# 2-STM32H563.net
KiCad netlist of a schematic drawn in Altium Designer
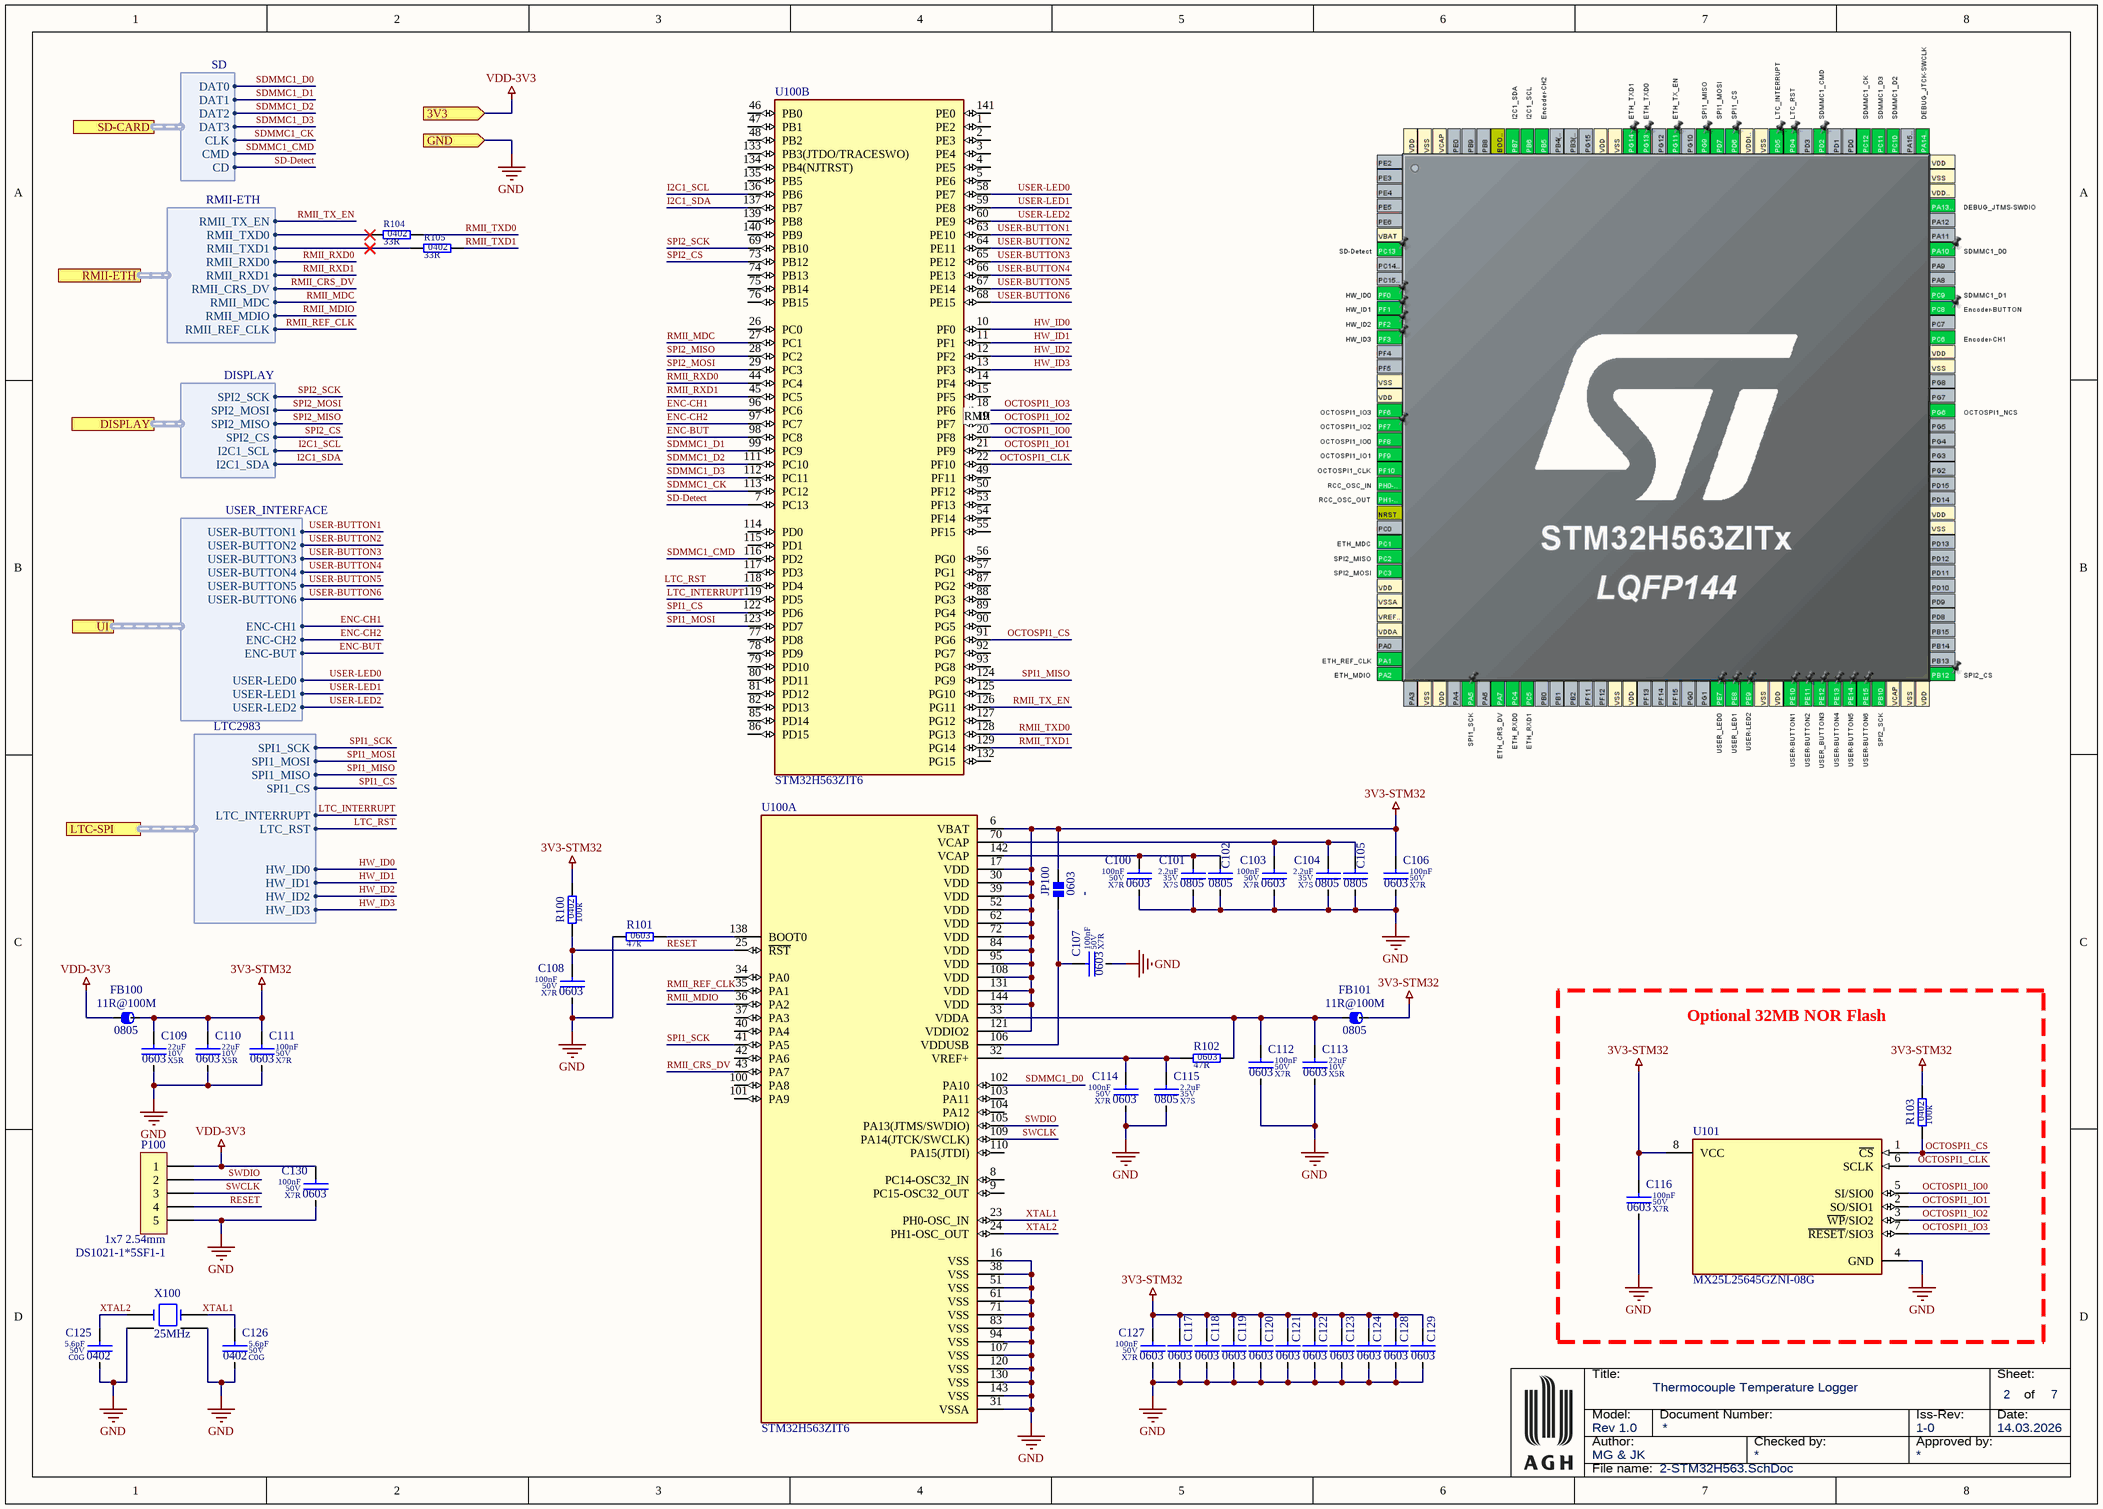
[diagram p0: 2-STM32H563.SchDoc]

(export (version "E")
  (design (tool "Eeschema 10.0.6"))
  (components
    (comp (ref "C100")
      (value "100nF")
      (footprint "C_0603_1608")
      (description "Capacitor")
      (fields
        (field (name "DIELECTRIC") "X7R")
        (field (name "VOLTAGE") "50V")
        (field (name "SCH_FOOTPRINT") "0603")
        (field (name "PART NUMBER") "C_100nF_50V_X7R_0603_10_AECQ1")
        (field (name "MANUFACTURER") "Murata")
      )
      (libsource (lib "Library") (part "C"))
    )
    (comp (ref "C101")
      (value "2.2uF")
      (footprint "C_0805_2012")
      (description "Capacitor")
      (fields
        (field (name "DIELECTRIC") "X7S")
        (field (name "VOLTAGE") "35V")
        (field (name "SCH_FOOTPRINT") "0805")
        (field (name "PART NUMBER") "C_2.2uF_35V_X7S_0805_10_AECQ1")
        (field (name "MANUFACTURER") "Murata")
      )
      (libsource (lib "Library") (part "C"))
    )
    (comp (ref "C102")
      (value "Ceramic X7S")
      (footprint "C_0805_2012")
      (description "Capacitor")
      (fields
        (field (name "VOLTAGE") "35V")
        (field (name "SCH_FOOTPRINT") "0805")
        (field (name "PART NUMBER") "C_2.2uF_35V_X7S_0805_10_AECQ1")
      )
      (libsource (lib "Library") (part "C"))
    )
    (comp (ref "C103")
      (value "100nF")
      (footprint "C_0603_1608")
      (description "Capacitor")
      (fields
        (field (name "DIELECTRIC") "X7R")
        (field (name "VOLTAGE") "50V")
        (field (name "SCH_FOOTPRINT") "0603")
        (field (name "PART NUMBER") "C_100nF_50V_X7R_0603_10_AECQ1")
        (field (name "MANUFACTURER") "Murata")
      )
      (libsource (lib "Library") (part "C"))
    )
    (comp (ref "C104")
      (value "2.2uF")
      (footprint "C_0805_2012")
      (description "Capacitor")
      (fields
        (field (name "DIELECTRIC") "X7S")
        (field (name "VOLTAGE") "35V")
        (field (name "SCH_FOOTPRINT") "0805")
        (field (name "PART NUMBER") "C_2.2uF_35V_X7S_0805_10_AECQ1")
        (field (name "MANUFACTURER") "Murata")
      )
      (libsource (lib "Library") (part "C"))
    )
    (comp (ref "C105")
      (value "Ceramic X7S")
      (footprint "C_0805_2012")
      (description "Capacitor")
      (fields
        (field (name "VOLTAGE") "35V")
        (field (name "SCH_FOOTPRINT") "0805")
        (field (name "PART NUMBER") "C_2.2uF_35V_X7S_0805_10_AECQ1")
      )
      (libsource (lib "Library") (part "C"))
    )
    (comp (ref "C106")
      (value "100nF")
      (footprint "C_0603_1608")
      (description "Capacitor")
      (fields
        (field (name "DIELECTRIC") "X7R")
        (field (name "VOLTAGE") "50V")
        (field (name "SCH_FOOTPRINT") "0603")
        (field (name "PART NUMBER") "C_100nF_50V_X7R_0603_10_AECQ1")
        (field (name "MANUFACTURER") "Murata")
      )
      (libsource (lib "Library") (part "C"))
    )
    (comp (ref "C107")
      (value "100nF")
      (footprint "C_0603_1608")
      (description "Capacitor")
      (fields
        (field (name "DIELECTRIC") "X7R")
        (field (name "VOLTAGE") "50V")
        (field (name "SCH_FOOTPRINT") "0603")
        (field (name "PART NUMBER") "C_100nF_50V_X7R_0603_10_AECQ1")
        (field (name "MANUFACTURER") "Murata")
      )
      (libsource (lib "Library") (part "C"))
    )
    (comp (ref "C108")
      (value "100nF")
      (footprint "C_0603_1608")
      (description "Capacitor")
      (fields
        (field (name "DIELECTRIC") "X7R")
        (field (name "VOLTAGE") "50V")
        (field (name "SCH_FOOTPRINT") "0603")
        (field (name "PART NUMBER") "C_100nF_50V_X7R_0603_10_AECQ1")
        (field (name "MANUFACTURER") "Murata")
      )
      (libsource (lib "Library") (part "C"))
    )
    (comp (ref "C109")
      (value "22uF")
      (footprint "C_0603_1608")
      (description "Capacitor")
      (fields
        (field (name "DIELECTRIC") "X5R")
        (field (name "VOLTAGE") "10V")
        (field (name "SCH_FOOTPRINT") "0603")
        (field (name "PART NUMBER") "C_22uF_10V_X5R_0603_20")
        (field (name "MANUFACTURER") "Murata")
      )
      (libsource (lib "Library") (part "C"))
    )
    (comp (ref "C110")
      (value "22uF")
      (footprint "C_0603_1608")
      (description "Capacitor")
      (fields
        (field (name "DIELECTRIC") "X5R")
        (field (name "VOLTAGE") "10V")
        (field (name "SCH_FOOTPRINT") "0603")
        (field (name "PART NUMBER") "C_22uF_10V_X5R_0603_20")
        (field (name "MANUFACTURER") "Murata")
      )
      (libsource (lib "Library") (part "C"))
    )
    (comp (ref "C111")
      (value "100nF")
      (footprint "C_0603_1608")
      (description "Capacitor")
      (fields
        (field (name "DIELECTRIC") "X7R")
        (field (name "VOLTAGE") "50V")
        (field (name "SCH_FOOTPRINT") "0603")
        (field (name "PART NUMBER") "C_100nF_50V_X7R_0603_10_AECQ1")
        (field (name "MANUFACTURER") "Murata")
      )
      (libsource (lib "Library") (part "C"))
    )
    (comp (ref "C112")
      (value "100nF")
      (footprint "C_0603_1608")
      (description "Capacitor")
      (fields
        (field (name "DIELECTRIC") "X7R")
        (field (name "VOLTAGE") "50V")
        (field (name "SCH_FOOTPRINT") "0603")
        (field (name "PART NUMBER") "C_100nF_50V_X7R_0603_10_AECQ1")
        (field (name "MANUFACTURER") "Murata")
      )
      (libsource (lib "Library") (part "C"))
    )
    (comp (ref "C113")
      (value "22uF")
      (footprint "C_0603_1608")
      (description "Capacitor")
      (fields
        (field (name "DIELECTRIC") "X5R")
        (field (name "VOLTAGE") "10V")
        (field (name "SCH_FOOTPRINT") "0603")
        (field (name "PART NUMBER") "C_22uF_10V_X5R_0603_20")
        (field (name "MANUFACTURER") "Murata")
      )
      (libsource (lib "Library") (part "C"))
    )
    (comp (ref "C114")
      (value "100nF")
      (footprint "C_0603_1608")
      (description "Capacitor")
      (fields
        (field (name "DIELECTRIC") "X7R")
        (field (name "VOLTAGE") "50V")
        (field (name "SCH_FOOTPRINT") "0603")
        (field (name "PART NUMBER") "C_100nF_50V_X7R_0603_10_AECQ1")
        (field (name "MANUFACTURER") "Murata")
      )
      (libsource (lib "Library") (part "C"))
    )
    (comp (ref "C115")
      (value "2.2uF")
      (footprint "C_0805_2012")
      (description "Capacitor")
      (fields
        (field (name "DIELECTRIC") "X7S")
        (field (name "VOLTAGE") "35V")
        (field (name "SCH_FOOTPRINT") "0805")
        (field (name "PART NUMBER") "C_2.2uF_35V_X7S_0805_10_AECQ1")
        (field (name "MANUFACTURER") "Murata")
      )
      (libsource (lib "Library") (part "C"))
    )
    (comp (ref "C116")
      (value "100nF")
      (footprint "C_0603_1608")
      (description "Capacitor")
      (fields
        (field (name "DIELECTRIC") "X7R")
        (field (name "VOLTAGE") "50V")
        (field (name "SCH_FOOTPRINT") "0603")
        (field (name "PART NUMBER") "C_100nF_50V_X7R_0603_10_AECQ1")
        (field (name "MANUFACTURER") "Murata")
      )
      (libsource (lib "Library") (part "C"))
    )
    (comp (ref "C117")
      (value "Ceramic X7R")
      (footprint "C_0603_1608")
      (description "Capacitor")
      (fields
        (field (name "VOLTAGE") "50V")
        (field (name "SCH_FOOTPRINT") "0603")
        (field (name "PART NUMBER") "C_100nF_50V_X7R_0603_10_AECQ1")
      )
      (libsource (lib "Library") (part "C"))
    )
    (comp (ref "C118")
      (value "Ceramic X7R")
      (footprint "C_0603_1608")
      (description "Capacitor")
      (fields
        (field (name "VOLTAGE") "50V")
        (field (name "SCH_FOOTPRINT") "0603")
        (field (name "PART NUMBER") "C_100nF_50V_X7R_0603_10_AECQ1")
      )
      (libsource (lib "Library") (part "C"))
    )
    (comp (ref "C119")
      (value "Ceramic X7R")
      (footprint "C_0603_1608")
      (description "Capacitor")
      (fields
        (field (name "VOLTAGE") "50V")
        (field (name "SCH_FOOTPRINT") "0603")
        (field (name "PART NUMBER") "C_100nF_50V_X7R_0603_10_AECQ1")
      )
      (libsource (lib "Library") (part "C"))
    )
    (comp (ref "C120")
      (value "Ceramic X7R")
      (footprint "C_0603_1608")
      (description "Capacitor")
      (fields
        (field (name "VOLTAGE") "50V")
        (field (name "SCH_FOOTPRINT") "0603")
        (field (name "PART NUMBER") "C_100nF_50V_X7R_0603_10_AECQ1")
      )
      (libsource (lib "Library") (part "C"))
    )
    (comp (ref "C121")
      (value "Ceramic X7R")
      (footprint "C_0603_1608")
      (description "Capacitor")
      (fields
        (field (name "VOLTAGE") "50V")
        (field (name "SCH_FOOTPRINT") "0603")
        (field (name "PART NUMBER") "C_100nF_50V_X7R_0603_10_AECQ1")
      )
      (libsource (lib "Library") (part "C"))
    )
    (comp (ref "C122")
      (value "Ceramic X7R")
      (footprint "C_0603_1608")
      (description "Capacitor")
      (fields
        (field (name "VOLTAGE") "50V")
        (field (name "SCH_FOOTPRINT") "0603")
        (field (name "PART NUMBER") "C_100nF_50V_X7R_0603_10_AECQ1")
      )
      (libsource (lib "Library") (part "C"))
    )
    (comp (ref "C123")
      (value "Ceramic X7R")
      (footprint "C_0603_1608")
      (description "Capacitor")
      (fields
        (field (name "VOLTAGE") "50V")
        (field (name "SCH_FOOTPRINT") "0603")
        (field (name "PART NUMBER") "C_100nF_50V_X7R_0603_10_AECQ1")
      )
      (libsource (lib "Library") (part "C"))
    )
    (comp (ref "C124")
      (value "Ceramic X7R")
      (footprint "C_0603_1608")
      (description "Capacitor")
      (fields
        (field (name "VOLTAGE") "50V")
        (field (name "SCH_FOOTPRINT") "0603")
        (field (name "PART NUMBER") "C_100nF_50V_X7R_0603_10_AECQ1")
      )
      (libsource (lib "Library") (part "C"))
    )
    (comp (ref "C125")
      (value "5.6pF")
      (footprint "C_0402_1005")
      (description "Capacitor")
      (fields
        (field (name "DIELECTRIC") "C0G")
        (field (name "VOLTAGE") "50V")
        (field (name "SCH_FOOTPRINT") "0402")
        (field (name "PART NUMBER") "C_5.6pF_50V_C0G_0402_2_AECQ1")
        (field (name "MANUFACTURER") "Murata")
      )
      (libsource (lib "Library") (part "C"))
    )
    (comp (ref "C126")
      (value "5.6pF")
      (footprint "C_0402_1005")
      (description "Capacitor")
      (fields
        (field (name "DIELECTRIC") "C0G")
        (field (name "VOLTAGE") "50V")
        (field (name "SCH_FOOTPRINT") "0402")
        (field (name "PART NUMBER") "C_5.6pF_50V_C0G_0402_2_AECQ1")
        (field (name "MANUFACTURER") "Murata")
      )
      (libsource (lib "Library") (part "C"))
    )
    (comp (ref "C127")
      (value "100nF")
      (footprint "C_0603_1608")
      (description "Capacitor")
      (fields
        (field (name "DIELECTRIC") "X7R")
        (field (name "VOLTAGE") "50V")
        (field (name "SCH_FOOTPRINT") "0603")
        (field (name "PART NUMBER") "C_100nF_50V_X7R_0603_10_AECQ1")
        (field (name "MANUFACTURER") "Murata")
      )
      (libsource (lib "Library") (part "C"))
    )
    (comp (ref "C128")
      (value "Ceramic X7R")
      (footprint "C_0603_1608")
      (description "Capacitor")
      (fields
        (field (name "VOLTAGE") "50V")
        (field (name "SCH_FOOTPRINT") "0603")
        (field (name "PART NUMBER") "C_100nF_50V_X7R_0603_10_AECQ1")
      )
      (libsource (lib "Library") (part "C"))
    )
    (comp (ref "C129")
      (value "Ceramic X7R")
      (footprint "C_0603_1608")
      (description "Capacitor")
      (fields
        (field (name "VOLTAGE") "50V")
        (field (name "SCH_FOOTPRINT") "0603")
        (field (name "PART NUMBER") "C_100nF_50V_X7R_0603_10_AECQ1")
      )
      (libsource (lib "Library") (part "C"))
    )
    (comp (ref "C130")
      (value "100nF")
      (footprint "C_0603_1608")
      (description "Capacitor")
      (fields
        (field (name "DIELECTRIC") "X7R")
        (field (name "VOLTAGE") "50V")
        (field (name "SCH_FOOTPRINT") "0603")
        (field (name "PART NUMBER") "C_100nF_50V_X7R_0603_10_AECQ1")
        (field (name "MANUFACTURER") "Murata")
      )
      (libsource (lib "Library") (part "C"))
    )
    (comp (ref "FB100")
      (value "11R@100M")
      (footprint "FB_0805_2012")
      (description "Ferrite Bead")
      (fields
        (field (name "SCH_FOOTPRINT") "0805")
        (field (name "PART NUMBER") "FB_2508051107Y0")
        (field (name "MANUFACTURER") "Fair-Rite")
      )
      (libsource (lib "Library") (part "FB"))
    )
    (comp (ref "FB101")
      (value "11R@100M")
      (footprint "FB_0805_2012")
      (description "Ferrite Bead")
      (fields
        (field (name "SCH_FOOTPRINT") "0805")
        (field (name "PART NUMBER") "FB_2508051107Y0")
        (field (name "MANUFACTURER") "Fair-Rite")
      )
      (libsource (lib "Library") (part "FB"))
    )
    (comp (ref "JP100")
      (value "-")
      (footprint "JP_0603_1608")
      (fields
        (field (name "SCH_FOOTPRINT") "0603")
        (field (name "PART NUMBER") "JP_0603_1608")
        (field (name "Comment") "Solder Jumper 0603/1608")
      )
      (libsource (lib "Library") (part "JP"))
    )
    (comp (ref "P100")
      (value "DS1021-1*5SF1-1")
      (footprint "P_HEADER_1x5_2.54")
      (description "Pin Header")
      (fields
        (field (name "SCH_FOOTPRINT") "1x7 2.54mm")
        (field (name "PART NUMBER") "P_HEADER_1x5_2.54")
        (field (name "MANUFACTURER") "Connfly")
      )
      (libsource (lib "Library") (part "P_HEADER_1x5"))
    )
    (comp (ref "R100")
      (value "100k")
      (footprint "R_0402_1005")
      (fields
        (field (name "SCH_FOOTPRINT") "0402")
        (field (name "PART NUMBER") "R_100k_0402_1")
        (field (name "VOLTAGE") "50V")
        (field (name "POWER") "63mW")
      )
      (libsource (lib "Library") (part "R"))
    )
    (comp (ref "R101")
      (value "47k")
      (footprint "R_0603_1608")
      (fields
        (field (name "SCH_FOOTPRINT") "0603")
        (field (name "PART NUMBER") "R_47k_0603_1_AECQ0")
        (field (name "VOLTAGE") "75V")
        (field (name "POWER") "100mW")
      )
      (libsource (lib "Library") (part "R"))
    )
    (comp (ref "R102")
      (value "47R")
      (footprint "R_0603_1608")
      (fields
        (field (name "SCH_FOOTPRINT") "0603")
        (field (name "PART NUMBER") "R_47R_0603_1")
        (field (name "VOLTAGE") "75V")
        (field (name "POWER") "100mW")
      )
      (libsource (lib "Library") (part "R"))
    )
    (comp (ref "R103")
      (value "100k")
      (footprint "R_0402_1005")
      (fields
        (field (name "SCH_FOOTPRINT") "0402")
        (field (name "PART NUMBER") "R_100k_0402_1")
        (field (name "VOLTAGE") "50V")
        (field (name "POWER") "63mW")
      )
      (libsource (lib "Library") (part "R"))
    )
    (comp (ref "R104")
      (value "33R")
      (footprint "R_0402_1005")
      (fields
        (field (name "SCH_FOOTPRINT") "0402")
        (field (name "PART NUMBER") "R_33R_0402_1_AECQ0")
        (field (name "VOLTAGE") "50V")
        (field (name "POWER") "100mW")
      )
      (libsource (lib "Library") (part "R"))
    )
    (comp (ref "R105")
      (value "33R")
      (footprint "R_0402_1005")
      (fields
        (field (name "SCH_FOOTPRINT") "0402")
        (field (name "PART NUMBER") "R_33R_0402_1_AECQ0")
        (field (name "VOLTAGE") "50V")
        (field (name "POWER") "100mW")
      )
      (libsource (lib "Library") (part "R"))
    )
    (comp (ref "U100")
      (value "STM32H563ZIT6")
      (footprint "QFP50P2200X2200X160-144N")
      (description "ARMÂ® CortexÂ®-M33 STM32H5 Microcontroller IC 32-Bit 250MHz 2MB (2M x 8) FLASH 144-LQFP (20x20)")
      (fields (field (name "MF") "STMicroelectronics"))
      (libsource (lib "STM32H563ZIT6") (part "STM32H563ZIT6"))
    )
    (comp (ref "U101")
      (value "MX25L25645GZNI-08G")
      (footprint "SOIC-8-4X5X18")
      (description "IC FLSH 256MBIT SPI 120MHZ 8WSON")
      (libsource (lib "MX25L25645GM2I-10G") (part "MX25L25645GM2I-10G"))
    )
    (comp (ref "X100")
      (value "25MHz")
      (footprint "X_2x1.6_4PIN")
      (fields
        (field (name "PART NUMBER") "NX2016SA-25.000M-STD-CZS-1")
        (field (name "MANUFACTURER") "NDK")
        (field (name "Comment") "32 MHz Oscilator")
      )
      (libsource (lib "Library") (part "X_GENERIC_4PIN"))
    )
  )
  (nets
    (net (code "6") (name "/ENC-BUT") (class "Default")
      (node (ref "U100") (pin "98") (pinfunction "PC8_98") (pintype "bidirectional"))
    )
    (net (code "7") (name "/ENC-CH1") (class "Default")
      (node (ref "U100") (pin "96") (pinfunction "PC6_96") (pintype "bidirectional"))
    )
    (net (code "8") (name "/ENC-CH2") (class "Default")
      (node (ref "U100") (pin "97") (pinfunction "PC7_97") (pintype "bidirectional"))
    )
    (net (code "9") (name "/HW_ID0") (class "Default")
      (node (ref "U100") (pin "10") (pinfunction "PF0_10") (pintype "bidirectional"))
    )
    (net (code "10") (name "/HW_ID1") (class "Default")
      (node (ref "U100") (pin "11") (pinfunction "PF1_11") (pintype "bidirectional"))
    )
    (net (code "11") (name "/HW_ID2") (class "Default")
      (node (ref "U100") (pin "12") (pinfunction "PF2_12") (pintype "bidirectional"))
    )
    (net (code "12") (name "/HW_ID3") (class "Default")
      (node (ref "U100") (pin "13") (pinfunction "PF3_13") (pintype "bidirectional"))
    )
    (net (code "13") (name "/I2C1_SCL") (class "Default")
      (node (ref "U100") (pin "136") (pinfunction "PB6_136") (pintype "bidirectional"))
    )
    (net (code "14") (name "/I2C1_SDA") (class "Default")
      (node (ref "U100") (pin "137") (pinfunction "PB7_137") (pintype "bidirectional"))
    )
    (net (code "15") (name "/LTC_INTERRUPT") (class "Default")
      (node (ref "U100") (pin "119") (pinfunction "PD5_119") (pintype "bidirectional"))
    )
    (net (code "16") (name "/LTC_RST") (class "Default")
      (node (ref "U100") (pin "118") (pinfunction "PD4_118") (pintype "bidirectional"))
    )
    (net (code "17") (name "/OCTOSPI1_CLK") (class "Default")
      (node (ref "U100") (pin "22") (pinfunction "PF10_22") (pintype "bidirectional"))
      (node (ref "U101") (pin "6") (pinfunction "SCLK_6") (pintype "input"))
    )
    (net (code "18") (name "/OCTOSPI1_CS") (class "Default")
      (node (ref "R103") (pin "1") (pinfunction "1_1") (pintype "passive"))
      (node (ref "U100") (pin "91") (pinfunction "PG6_91") (pintype "bidirectional"))
      (node (ref "U101") (pin "1") (pinfunction "~{CS}_1") (pintype "input"))
    )
    (net (code "19") (name "/OCTOSPI1_IO0") (class "Default")
      (node (ref "U100") (pin "20") (pinfunction "PF8_20") (pintype "bidirectional"))
      (node (ref "U101") (pin "5") (pinfunction "SI/SIO0_5") (pintype "bidirectional"))
    )
    (net (code "20") (name "/OCTOSPI1_IO1") (class "Default")
      (node (ref "U100") (pin "21") (pinfunction "PF9_21") (pintype "bidirectional"))
      (node (ref "U101") (pin "2") (pinfunction "SO/SIO1_2") (pintype "bidirectional"))
    )
    (net (code "21") (name "/OCTOSPI1_IO2") (class "Default")
      (node (ref "U100") (pin "19") (pinfunction "PF7_19") (pintype "bidirectional"))
      (node (ref "U101") (pin "3") (pinfunction "~{WP}/SIO2_3") (pintype "bidirectional"))
    )
    (net (code "22") (name "/OCTOSPI1_IO3") (class "Default")
      (node (ref "U100") (pin "18") (pinfunction "PF6_18") (pintype "bidirectional"))
      (node (ref "U101") (pin "7") (pinfunction "~{RESET}/SIO3_7") (pintype "bidirectional"))
    )
    (net (code "23") (name "/RESET") (class "Default")
      (node (ref "C108") (pin "1") (pinfunction "1_1") (pintype "passive"))
      (node (ref "P100") (pin "4") (pinfunction "4_4") (pintype "passive"))
      (node (ref "R100") (pin "1") (pinfunction "1_1") (pintype "passive"))
      (node (ref "U100") (pin "25") (pinfunction "~{RST}_25") (pintype "bidirectional"))
    )
    (net (code "24") (name "/RMII_CRS_DV") (class "Default")
      (node (ref "U100") (pin "43") (pinfunction "PA7_43") (pintype "bidirectional"))
    )
    (net (code "25") (name "/RMII_MDC") (class "Default")
      (node (ref "U100") (pin "27") (pinfunction "PC1_27") (pintype "bidirectional"))
    )
    (net (code "26") (name "/RMII_MDIO") (class "Default")
      (node (ref "U100") (pin "36") (pinfunction "PA2_36") (pintype "bidirectional"))
    )
    (net (code "27") (name "/RMII_REF_CLK") (class "Default")
      (node (ref "U100") (pin "35") (pinfunction "PA1_35") (pintype "bidirectional"))
    )
    (net (code "28") (name "/RMII_RXD0") (class "Default")
      (node (ref "U100") (pin "44") (pinfunction "PC4_44") (pintype "bidirectional"))
    )
    (net (code "29") (name "/RMII_RXD1") (class "Default")
      (node (ref "U100") (pin "45") (pinfunction "PC5_45") (pintype "bidirectional"))
    )
    (net (code "30") (name "/RMII_TXD0") (class "Default")
      (node (ref "R104") (pin "2") (pinfunction "2_2") (pintype "passive"))
      (node (ref "U100") (pin "128") (pinfunction "PG13_128") (pintype "bidirectional"))
    )
    (net (code "31") (name "/RMII_TXD1") (class "Default")
      (node (ref "R105") (pin "2") (pinfunction "2_2") (pintype "passive"))
      (node (ref "U100") (pin "129") (pinfunction "PG14_129") (pintype "bidirectional"))
    )
    (net (code "32") (name "/RMII_TX_EN") (class "Default")
      (node (ref "U100") (pin "126") (pinfunction "PG11_126") (pintype "bidirectional"))
    )
    (net (code "33") (name "/SD-Detect") (class "Default")
      (node (ref "U100") (pin "7") (pinfunction "PC13_7") (pintype "bidirectional"))
    )
    (net (code "34") (name "/SDMMC1_CK") (class "Default")
      (node (ref "U100") (pin "113") (pinfunction "PC12_113") (pintype "bidirectional"))
    )
    (net (code "35") (name "/SDMMC1_CMD") (class "Default")
      (node (ref "U100") (pin "116") (pinfunction "PD2_116") (pintype "bidirectional"))
    )
    (net (code "36") (name "/SDMMC1_D0") (class "Default")
      (node (ref "U100") (pin "102") (pinfunction "PA10_102") (pintype "bidirectional"))
    )
    (net (code "37") (name "/SDMMC1_D1") (class "Default")
      (node (ref "U100") (pin "99") (pinfunction "PC9_99") (pintype "bidirectional"))
    )
    (net (code "38") (name "/SDMMC1_D2") (class "Default")
      (node (ref "U100") (pin "111") (pinfunction "PC10_111") (pintype "bidirectional"))
    )
    (net (code "39") (name "/SDMMC1_D3") (class "Default")
      (node (ref "U100") (pin "112") (pinfunction "PC11_112") (pintype "bidirectional"))
    )
    (net (code "40") (name "/SPI1_CS") (class "Default")
      (node (ref "U100") (pin "122") (pinfunction "PD6_122") (pintype "bidirectional"))
    )
    (net (code "41") (name "/SPI1_MISO") (class "Default")
      (node (ref "U100") (pin "124") (pinfunction "PG9_124") (pintype "bidirectional"))
    )
    (net (code "42") (name "/SPI1_MOSI") (class "Default")
      (node (ref "U100") (pin "123") (pinfunction "PD7_123") (pintype "bidirectional"))
    )
    (net (code "43") (name "/SPI1_SCK") (class "Default")
      (node (ref "U100") (pin "41") (pinfunction "PA5_41") (pintype "bidirectional"))
    )
    (net (code "44") (name "/SPI2_CS") (class "Default")
      (node (ref "U100") (pin "73") (pinfunction "PB12_73") (pintype "bidirectional"))
    )
    (net (code "45") (name "/SPI2_MISO") (class "Default")
      (node (ref "U100") (pin "28") (pinfunction "PC2_28") (pintype "bidirectional"))
    )
    (net (code "46") (name "/SPI2_MOSI") (class "Default")
      (node (ref "U100") (pin "29") (pinfunction "PC3_29") (pintype "bidirectional"))
    )
    (net (code "47") (name "/SPI2_SCK") (class "Default")
      (node (ref "U100") (pin "69") (pinfunction "PB10_69") (pintype "bidirectional"))
    )
    (net (code "48") (name "/SWCLK") (class "Default")
      (node (ref "P100") (pin "3") (pinfunction "3_3") (pintype "passive"))
      (node (ref "U100") (pin "109") (pinfunction "PA14(JTCK/SWCLK)_109") (pintype "bidirectional"))
    )
    (net (code "49") (name "/SWDIO") (class "Default")
      (node (ref "P100") (pin "2") (pinfunction "2_2") (pintype "passive"))
      (node (ref "U100") (pin "105") (pinfunction "PA13(JTMS/SWDIO)_105") (pintype "bidirectional"))
    )
    (net (code "50") (name "/USER-BUTTON1") (class "Default")
      (node (ref "U100") (pin "63") (pinfunction "PE10_63") (pintype "bidirectional"))
    )
    (net (code "51") (name "/USER-BUTTON2") (class "Default")
      (node (ref "U100") (pin "64") (pinfunction "PE11_64") (pintype "bidirectional"))
    )
    (net (code "52") (name "/USER-BUTTON3") (class "Default")
      (node (ref "U100") (pin "65") (pinfunction "PE12_65") (pintype "bidirectional"))
    )
    (net (code "53") (name "/USER-BUTTON4") (class "Default")
      (node (ref "U100") (pin "66") (pinfunction "PE13_66") (pintype "bidirectional"))
    )
    (net (code "54") (name "/USER-BUTTON5") (class "Default")
      (node (ref "U100") (pin "67") (pinfunction "PE14_67") (pintype "bidirectional"))
    )
    (net (code "55") (name "/USER-BUTTON6") (class "Default")
      (node (ref "U100") (pin "68") (pinfunction "PE15_68") (pintype "bidirectional"))
    )
    (net (code "56") (name "/USER-LED0") (class "Default")
      (node (ref "U100") (pin "58") (pinfunction "PE7_58") (pintype "bidirectional"))
    )
    (net (code "57") (name "/USER-LED1") (class "Default")
      (node (ref "U100") (pin "59") (pinfunction "PE8_59") (pintype "bidirectional"))
    )
    (net (code "58") (name "/USER-LED2") (class "Default")
      (node (ref "U100") (pin "60") (pinfunction "PE9_60") (pintype "bidirectional"))
    )
    (net (code "59") (name "/XTAL1") (class "Default")
      (node (ref "C126") (pin "1") (pinfunction "1_1") (pintype "passive"))
      (node (ref "U100") (pin "23") (pinfunction "PH0-OSC_IN_23") (pintype "bidirectional"))
      (node (ref "X100") (pin "1") (pinfunction "1_1") (pintype "passive"))
    )
    (net (code "60") (name "/XTAL2") (class "Default")
      (node (ref "C125") (pin "1") (pinfunction "1_1") (pintype "passive"))
      (node (ref "U100") (pin "24") (pinfunction "PH1-OSC_OUT_24") (pintype "bidirectional"))
      (node (ref "X100") (pin "3") (pinfunction "3_3") (pintype "passive"))
    )
    (net (code "66") (name "3V3-STM32") (class "Default")
      (node (ref "C106") (pin "1") (pinfunction "1_1") (pintype "passive"))
      (node (ref "C109") (pin "1") (pinfunction "1_1") (pintype "passive"))
      (node (ref "C110") (pin "1") (pinfunction "1_1") (pintype "passive"))
      (node (ref "C111") (pin "1") (pinfunction "1_1") (pintype "passive"))
      (node (ref "C116") (pin "1") (pinfunction "1_1") (pintype "passive"))
      (node (ref "C117") (pin "1") (pinfunction "1_1") (pintype "passive"))
      (node (ref "C118") (pin "1") (pinfunction "1_1") (pintype "passive"))
      (node (ref "C119") (pin "1") (pinfunction "1_1") (pintype "passive"))
      (node (ref "C120") (pin "1") (pinfunction "1_1") (pintype "passive"))
      (node (ref "C121") (pin "1") (pinfunction "1_1") (pintype "passive"))
      (node (ref "C122") (pin "1") (pinfunction "1_1") (pintype "passive"))
      (node (ref "C123") (pin "1") (pinfunction "1_1") (pintype "passive"))
      (node (ref "C124") (pin "1") (pinfunction "1_1") (pintype "passive"))
      (node (ref "C127") (pin "1") (pinfunction "1_1") (pintype "passive"))
      (node (ref "C128") (pin "1") (pinfunction "1_1") (pintype "passive"))
      (node (ref "C129") (pin "1") (pinfunction "1_1") (pintype "passive"))
      (node (ref "FB100") (pin "2") (pintype "passive"))
      (node (ref "FB101") (pin "2") (pintype "passive"))
      (node (ref "JP100") (pin "2") (pinfunction "2_2") (pintype "passive"))
      (node (ref "R100") (pin "2") (pinfunction "2_2") (pintype "passive"))
      (node (ref "R103") (pin "2") (pinfunction "2_2") (pintype "passive"))
      (node (ref "U100") (pin "108") (pinfunction "VDD_108") (pintype "power_in"))
      (node (ref "U100") (pin "121") (pinfunction "VDDIO2_121") (pintype "power_in"))
      (node (ref "U100") (pin "131") (pinfunction "VDD_131") (pintype "power_in"))
      (node (ref "U100") (pin "144") (pinfunction "VDD_144") (pintype "power_in"))
      (node (ref "U100") (pin "17") (pinfunction "VDD_17") (pintype "power_in"))
      (node (ref "U100") (pin "30") (pinfunction "VDD_30") (pintype "power_in"))
      (node (ref "U100") (pin "39") (pinfunction "VDD_39") (pintype "power_in"))
      (node (ref "U100") (pin "52") (pinfunction "VDD_52") (pintype "power_in"))
      (node (ref "U100") (pin "6") (pinfunction "VBAT_6") (pintype "power_in"))
      (node (ref "U100") (pin "62") (pinfunction "VDD_62") (pintype "power_in"))
      (node (ref "U100") (pin "72") (pinfunction "VDD_72") (pintype "power_in"))
      (node (ref "U100") (pin "84") (pinfunction "VDD_84") (pintype "power_in"))
      (node (ref "U100") (pin "95") (pinfunction "VDD_95") (pintype "power_in"))
      (node (ref "U101") (pin "8") (pinfunction "VCC_8") (pintype "power_in"))
    )
    (net (code "67") (name "GND") (class "Default")
      (node (ref "C100") (pin "2") (pinfunction "2_2") (pintype "passive"))
      (node (ref "C101") (pin "2") (pinfunction "2_2") (pintype "passive"))
      (node (ref "C102") (pin "2") (pinfunction "2_2") (pintype "passive"))
      (node (ref "C103") (pin "2") (pinfunction "2_2") (pintype "passive"))
      (node (ref "C104") (pin "2") (pinfunction "2_2") (pintype "passive"))
      (node (ref "C105") (pin "2") (pinfunction "2_2") (pintype "passive"))
      (node (ref "C106") (pin "2") (pinfunction "2_2") (pintype "passive"))
      (node (ref "C107") (pin "2") (pinfunction "2_2") (pintype "passive"))
      (node (ref "C108") (pin "2") (pinfunction "2_2") (pintype "passive"))
      (node (ref "C109") (pin "2") (pinfunction "2_2") (pintype "passive"))
      (node (ref "C110") (pin "2") (pinfunction "2_2") (pintype "passive"))
      (node (ref "C111") (pin "2") (pinfunction "2_2") (pintype "passive"))
      (node (ref "C112") (pin "2") (pinfunction "2_2") (pintype "passive"))
      (node (ref "C113") (pin "2") (pinfunction "2_2") (pintype "passive"))
      (node (ref "C114") (pin "2") (pinfunction "2_2") (pintype "passive"))
      (node (ref "C115") (pin "2") (pinfunction "2_2") (pintype "passive"))
      (node (ref "C116") (pin "2") (pinfunction "2_2") (pintype "passive"))
      (node (ref "C117") (pin "2") (pinfunction "2_2") (pintype "passive"))
      (node (ref "C118") (pin "2") (pinfunction "2_2") (pintype "passive"))
      (node (ref "C119") (pin "2") (pinfunction "2_2") (pintype "passive"))
      (node (ref "C120") (pin "2") (pinfunction "2_2") (pintype "passive"))
      (node (ref "C121") (pin "2") (pinfunction "2_2") (pintype "passive"))
      (node (ref "C122") (pin "2") (pinfunction "2_2") (pintype "passive"))
      (node (ref "C123") (pin "2") (pinfunction "2_2") (pintype "passive"))
      (node (ref "C124") (pin "2") (pinfunction "2_2") (pintype "passive"))
      (node (ref "C125") (pin "2") (pinfunction "2_2") (pintype "passive"))
      (node (ref "C126") (pin "2") (pinfunction "2_2") (pintype "passive"))
      (node (ref "C127") (pin "2") (pinfunction "2_2") (pintype "passive"))
      (node (ref "C128") (pin "2") (pinfunction "2_2") (pintype "passive"))
      (node (ref "C129") (pin "2") (pinfunction "2_2") (pintype "passive"))
      (node (ref "C130") (pin "2") (pinfunction "2_2") (pintype "passive"))
      (node (ref "P100") (pin "5") (pinfunction "5_5") (pintype "passive"))
      (node (ref "R101") (pin "1") (pinfunction "1_1") (pintype "passive"))
      (node (ref "U100") (pin "107") (pinfunction "VSS_107") (pintype "passive"))
      (node (ref "U100") (pin "120") (pinfunction "VSS_120") (pintype "passive"))
      (node (ref "U100") (pin "130") (pinfunction "VSS_130") (pintype "passive"))
      (node (ref "U100") (pin "143") (pinfunction "VSS_143") (pintype "passive"))
      (node (ref "U100") (pin "16") (pinfunction "VSS_16") (pintype "passive"))
      (node (ref "U100") (pin "31") (pinfunction "VSSA_31") (pintype "passive"))
      (node (ref "U100") (pin "38") (pinfunction "VSS_38") (pintype "passive"))
      (node (ref "U100") (pin "51") (pinfunction "VSS_51") (pintype "passive"))
      (node (ref "U100") (pin "61") (pinfunction "VSS_61") (pintype "passive"))
      (node (ref "U100") (pin "71") (pinfunction "VSS_71") (pintype "passive"))
      (node (ref "U100") (pin "83") (pinfunction "VSS_83") (pintype "passive"))
      (node (ref "U100") (pin "94") (pinfunction "VSS_94") (pintype "passive"))
      (node (ref "U101") (pin "4") (pinfunction "GND_4") (pintype "passive"))
      (node (ref "X100") (pin "2") (pinfunction "GND_2") (pintype "passive"))
      (node (ref "X100") (pin "4") (pinfunction "GND_4") (pintype "passive"))
    )
    (net (code "68") (name "Net-(C100-Pad1)") (class "Default")
      (node (ref "C100") (pin "1") (pinfunction "1_1") (pintype "passive"))
      (node (ref "C101") (pin "1") (pinfunction "1_1") (pintype "passive"))
      (node (ref "C102") (pin "1") (pinfunction "1_1") (pintype "passive"))
      (node (ref "U100") (pin "142") (pinfunction "VCAP_142") (pintype "power_in"))
    )
    (net (code "69") (name "Net-(C103-Pad1)") (class "Default")
      (node (ref "C103") (pin "1") (pinfunction "1_1") (pintype "passive"))
      (node (ref "C104") (pin "1") (pinfunction "1_1") (pintype "passive"))
      (node (ref "C105") (pin "1") (pinfunction "1_1") (pintype "passive"))
      (node (ref "U100") (pin "70") (pinfunction "VCAP_70") (pintype "power_in"))
    )
    (net (code "70") (name "Net-(U100A-BOOT0)") (class "Default")
      (node (ref "R101") (pin "2") (pinfunction "2_2") (pintype "passive"))
      (node (ref "U100") (pin "138") (pinfunction "BOOT0_138") (pintype "passive"))
    )
    (net (code "71") (name "Net-(U100A-VDDA)") (class "Default")
      (node (ref "C112") (pin "1") (pinfunction "1_1") (pintype "passive"))
      (node (ref "C113") (pin "1") (pinfunction "1_1") (pintype "passive"))
      (node (ref "FB101") (pin "1") (pintype "passive"))
      (node (ref "R102") (pin "2") (pinfunction "2_2") (pintype "passive"))
      (node (ref "U100") (pin "33") (pinfunction "VDDA_33") (pintype "power_in"))
    )
    (net (code "72") (name "Net-(U100A-VDDUSB)") (class "Default")
      (node (ref "C107") (pin "1") (pinfunction "1_1") (pintype "passive"))
      (node (ref "JP100") (pin "1") (pinfunction "1_1") (pintype "passive"))
      (node (ref "U100") (pin "106") (pinfunction "VDDUSB_106") (pintype "power_in"))
    )
    (net (code "73") (name "Net-(U100A-VREF+)") (class "Default")
      (node (ref "C114") (pin "1") (pinfunction "1_1") (pintype "passive"))
      (node (ref "C115") (pin "1") (pinfunction "1_1") (pintype "passive"))
      (node (ref "R102") (pin "1") (pinfunction "1_1") (pintype "passive"))
      (node (ref "U100") (pin "32") (pinfunction "VREF+_32") (pintype "power_in"))
    )
    (net (code "74") (name "VDD-3V3") (class "Default")
      (node (ref "C130") (pin "1") (pinfunction "1_1") (pintype "passive"))
      (node (ref "FB100") (pin "1") (pintype "passive"))
      (node (ref "P100") (pin "1") (pinfunction "1_1") (pintype "passive"))
    )
    (net (code "75") (name "unconnected-(R104-Pad1)") (class "Default")
      (node (ref "R104") (pin "1") (pinfunction "1_1") (pintype "passive+no_connect"))
    )
    (net (code "76") (name "unconnected-(R105-Pad1)") (class "Default")
      (node (ref "R105") (pin "1") (pinfunction "1_1") (pintype "passive"))
    )
    (net (code "77") (name "unconnected-(U100A-PA0-Pad34)") (class "Default")
      (node (ref "U100") (pin "34") (pinfunction "PA0_34") (pintype "bidirectional"))
    )
    (net (code "78") (name "unconnected-(U100A-PA3-Pad37)") (class "Default")
      (node (ref "U100") (pin "37") (pinfunction "PA3_37") (pintype "bidirectional"))
    )
    (net (code "79") (name "unconnected-(U100A-PA4-Pad40)") (class "Default")
      (node (ref "U100") (pin "40") (pinfunction "PA4_40") (pintype "bidirectional"))
    )
    (net (code "80") (name "unconnected-(U100A-PA6-Pad42)") (class "Default")
      (node (ref "U100") (pin "42") (pinfunction "PA6_42") (pintype "bidirectional"))
    )
    (net (code "81") (name "unconnected-(U100A-PA8-Pad100)") (class "Default")
      (node (ref "U100") (pin "100") (pinfunction "PA8_100") (pintype "bidirectional"))
    )
    (net (code "82") (name "unconnected-(U100A-PA9-Pad101)") (class "Default")
      (node (ref "U100") (pin "101") (pinfunction "PA9_101") (pintype "bidirectional"))
    )
    (net (code "83") (name "unconnected-(U100A-PA11-Pad103)") (class "Default")
      (node (ref "U100") (pin "103") (pinfunction "PA11_103") (pintype "bidirectional"))
    )
    (net (code "84") (name "unconnected-(U100A-PA12-Pad104)") (class "Default")
      (node (ref "U100") (pin "104") (pinfunction "PA12_104") (pintype "bidirectional"))
    )
    (net (code "85") (name "unconnected-(U100A-PA15(JTDI)-Pad110)") (class "Default")
      (node (ref "U100") (pin "110") (pinfunction "PA15(JTDI)_110") (pintype "bidirectional"))
    )
    (net (code "86") (name "unconnected-(U100A-PC14-OSC32_IN-Pad8)") (class "Default")
      (node (ref "U100") (pin "8") (pinfunction "PC14-OSC32_IN_8") (pintype "bidirectional"))
    )
    (net (code "87") (name "unconnected-(U100A-PC15-OSC32_OUT-Pad9)") (class "Default")
      (node (ref "U100") (pin "9") (pinfunction "PC15-OSC32_OUT_9") (pintype "bidirectional"))
    )
    (net (code "88") (name "unconnected-(U100B-PB0-Pad46)") (class "Default")
      (node (ref "U100") (pin "46") (pinfunction "PB0_46") (pintype "bidirectional"))
    )
    (net (code "89") (name "unconnected-(U100B-PB1-Pad47)") (class "Default")
      (node (ref "U100") (pin "47") (pinfunction "PB1_47") (pintype "bidirectional"))
    )
    (net (code "90") (name "unconnected-(U100B-PB2-Pad48)") (class "Default")
      (node (ref "U100") (pin "48") (pinfunction "PB2_48") (pintype "bidirectional"))
    )
    (net (code "91") (name "unconnected-(U100B-PB3(JTDO{slash}TRACESWO)-Pad133)") (class "Default")
      (node (ref "U100") (pin "133") (pinfunction "PB3(JTDO/TRACESWO)_133") (pintype "bidirectional"))
    )
    (net (code "92") (name "unconnected-(U100B-PB4(NJTRST)-Pad134)") (class "Default")
      (node (ref "U100") (pin "134") (pinfunction "PB4(NJTRST)_134") (pintype "bidirectional"))
    )
    (net (code "93") (name "unconnected-(U100B-PB5-Pad135)") (class "Default")
      (node (ref "U100") (pin "135") (pinfunction "PB5_135") (pintype "bidirectional"))
    )
    (net (code "94") (name "unconnected-(U100B-PB8-Pad139)") (class "Default")
      (node (ref "U100") (pin "139") (pinfunction "PB8_139") (pintype "bidirectional"))
    )
    (net (code "95") (name "unconnected-(U100B-PB9-Pad140)") (class "Default")
      (node (ref "U100") (pin "140") (pinfunction "PB9_140") (pintype "bidirectional"))
    )
    (net (code "96") (name "unconnected-(U100B-PB13-Pad74)") (class "Default")
      (node (ref "U100") (pin "74") (pinfunction "PB13_74") (pintype "bidirectional"))
    )
    (net (code "97") (name "unconnected-(U100B-PB14-Pad75)") (class "Default")
      (node (ref "U100") (pin "75") (pinfunction "PB14_75") (pintype "bidirectional"))
    )
    (net (code "98") (name "unconnected-(U100B-PB15-Pad76)") (class "Default")
      (node (ref "U100") (pin "76") (pinfunction "PB15_76") (pintype "bidirectional"))
    )
    (net (code "99") (name "unconnected-(U100B-PC0-Pad26)") (class "Default")
      (node (ref "U100") (pin "26") (pinfunction "PC0_26") (pintype "bidirectional"))
    )
    (net (code "100") (name "unconnected-(U100B-PD0-Pad114)") (class "Default")
      (node (ref "U100") (pin "114") (pinfunction "PD0_114") (pintype "bidirectional"))
    )
    (net (code "101") (name "unconnected-(U100B-PD1-Pad115)") (class "Default")
      (node (ref "U100") (pin "115") (pinfunction "PD1_115") (pintype "bidirectional"))
    )
    (net (code "102") (name "unconnected-(U100B-PD3-Pad117)") (class "Default")
      (node (ref "U100") (pin "117") (pinfunction "PD3_117") (pintype "bidirectional"))
    )
    (net (code "103") (name "unconnected-(U100B-PD8-Pad77)") (class "Default")
      (node (ref "U100") (pin "77") (pinfunction "PD8_77") (pintype "bidirectional"))
    )
    (net (code "104") (name "unconnected-(U100B-PD9-Pad78)") (class "Default")
      (node (ref "U100") (pin "78") (pinfunction "PD9_78") (pintype "bidirectional"))
    )
    (net (code "105") (name "unconnected-(U100B-PD10-Pad79)") (class "Default")
      (node (ref "U100") (pin "79") (pinfunction "PD10_79") (pintype "bidirectional"))
    )
    (net (code "106") (name "unconnected-(U100B-PD11-Pad80)") (class "Default")
      (node (ref "U100") (pin "80") (pinfunction "PD11_80") (pintype "bidirectional"))
    )
    (net (code "107") (name "unconnected-(U100B-PD12-Pad81)") (class "Default")
      (node (ref "U100") (pin "81") (pinfunction "PD12_81") (pintype "bidirectional"))
    )
    (net (code "108") (name "unconnected-(U100B-PD13-Pad82)") (class "Default")
      (node (ref "U100") (pin "82") (pinfunction "PD13_82") (pintype "bidirectional"))
    )
    (net (code "109") (name "unconnected-(U100B-PD14-Pad85)") (class "Default")
      (node (ref "U100") (pin "85") (pinfunction "PD14_85") (pintype "bidirectional"))
    )
    (net (code "110") (name "unconnected-(U100B-PD15-Pad86)") (class "Default")
      (node (ref "U100") (pin "86") (pinfunction "PD15_86") (pintype "bidirectional"))
    )
    (net (code "111") (name "unconnected-(U100B-PE0-Pad141)") (class "Default")
      (node (ref "U100") (pin "141") (pinfunction "PE0_141") (pintype "bidirectional"))
    )
    (net (code "112") (name "unconnected-(U100B-PE2-Pad1)") (class "Default")
      (node (ref "U100") (pin "1") (pinfunction "PE2_1") (pintype "bidirectional"))
    )
    (net (code "113") (name "unconnected-(U100B-PE3-Pad2)") (class "Default")
      (node (ref "U100") (pin "2") (pinfunction "PE3_2") (pintype "bidirectional"))
    )
    (net (code "114") (name "unconnected-(U100B-PE4-Pad3)") (class "Default")
      (node (ref "U100") (pin "3") (pinfunction "PE4_3") (pintype "bidirectional"))
    )
    (net (code "115") (name "unconnected-(U100B-PE5-Pad4)") (class "Default")
      (node (ref "U100") (pin "4") (pinfunction "PE5_4") (pintype "bidirectional"))
    )
    (net (code "116") (name "unconnected-(U100B-PE6-Pad5)") (class "Default")
      (node (ref "U100") (pin "5") (pinfunction "PE6_5") (pintype "bidirectional"))
    )
    (net (code "117") (name "unconnected-(U100B-PF4-Pad14)") (class "Default")
      (node (ref "U100") (pin "14") (pinfunction "PF4_14") (pintype "bidirectional"))
    )
    (net (code "118") (name "unconnected-(U100B-PF5-Pad15)") (class "Default")
      (node (ref "U100") (pin "15") (pinfunction "PF5_15") (pintype "bidirectional"))
    )
    (net (code "119") (name "unconnected-(U100B-PF11-Pad49)") (class "Default")
      (node (ref "U100") (pin "49") (pinfunction "PF11_49") (pintype "bidirectional"))
    )
    (net (code "120") (name "unconnected-(U100B-PF12-Pad50)") (class "Default")
      (node (ref "U100") (pin "50") (pinfunction "PF12_50") (pintype "bidirectional"))
    )
    (net (code "121") (name "unconnected-(U100B-PF13-Pad53)") (class "Default")
      (node (ref "U100") (pin "53") (pinfunction "PF13_53") (pintype "bidirectional"))
    )
    (net (code "122") (name "unconnected-(U100B-PF14-Pad54)") (class "Default")
      (node (ref "U100") (pin "54") (pinfunction "PF14_54") (pintype "bidirectional"))
    )
    (net (code "123") (name "unconnected-(U100B-PF15-Pad55)") (class "Default")
      (node (ref "U100") (pin "55") (pinfunction "PF15_55") (pintype "bidirectional"))
    )
    (net (code "124") (name "unconnected-(U100B-PG0-Pad56)") (class "Default")
      (node (ref "U100") (pin "56") (pinfunction "PG0_56") (pintype "bidirectional"))
    )
    (net (code "125") (name "unconnected-(U100B-PG1-Pad57)") (class "Default")
      (node (ref "U100") (pin "57") (pinfunction "PG1_57") (pintype "bidirectional"))
    )
    (net (code "126") (name "unconnected-(U100B-PG2-Pad87)") (class "Default")
      (node (ref "U100") (pin "87") (pinfunction "PG2_87") (pintype "bidirectional"))
    )
    (net (code "127") (name "unconnected-(U100B-PG3-Pad88)") (class "Default")
      (node (ref "U100") (pin "88") (pinfunction "PG3_88") (pintype "bidirectional"))
    )
    (net (code "128") (name "unconnected-(U100B-PG4-Pad89)") (class "Default")
      (node (ref "U100") (pin "89") (pinfunction "PG4_89") (pintype "bidirectional"))
    )
    (net (code "129") (name "unconnected-(U100B-PG5-Pad90)") (class "Default")
      (node (ref "U100") (pin "90") (pinfunction "PG5_90") (pintype "bidirectional"))
    )
    (net (code "130") (name "unconnected-(U100B-PG7-Pad92)") (class "Default")
      (node (ref "U100") (pin "92") (pinfunction "PG7_92") (pintype "bidirectional"))
    )
    (net (code "131") (name "unconnected-(U100B-PG8-Pad93)") (class "Default")
      (node (ref "U100") (pin "93") (pinfunction "PG8_93") (pintype "bidirectional"))
    )
    (net (code "132") (name "unconnected-(U100B-PG10-Pad125)") (class "Default")
      (node (ref "U100") (pin "125") (pinfunction "PG10_125") (pintype "bidirectional"))
    )
    (net (code "133") (name "unconnected-(U100B-PG12-Pad127)") (class "Default")
      (node (ref "U100") (pin "127") (pinfunction "PG12_127") (pintype "bidirectional"))
    )
    (net (code "134") (name "unconnected-(U100B-PG15-Pad132)") (class "Default")
      (node (ref "U100") (pin "132") (pinfunction "PG15_132") (pintype "bidirectional"))
    )
  )
)
